# SCH_Dashboy_camera_NiMH_2023-03-14.net
KiCad netlist of a schematic drawn in EasyEDA
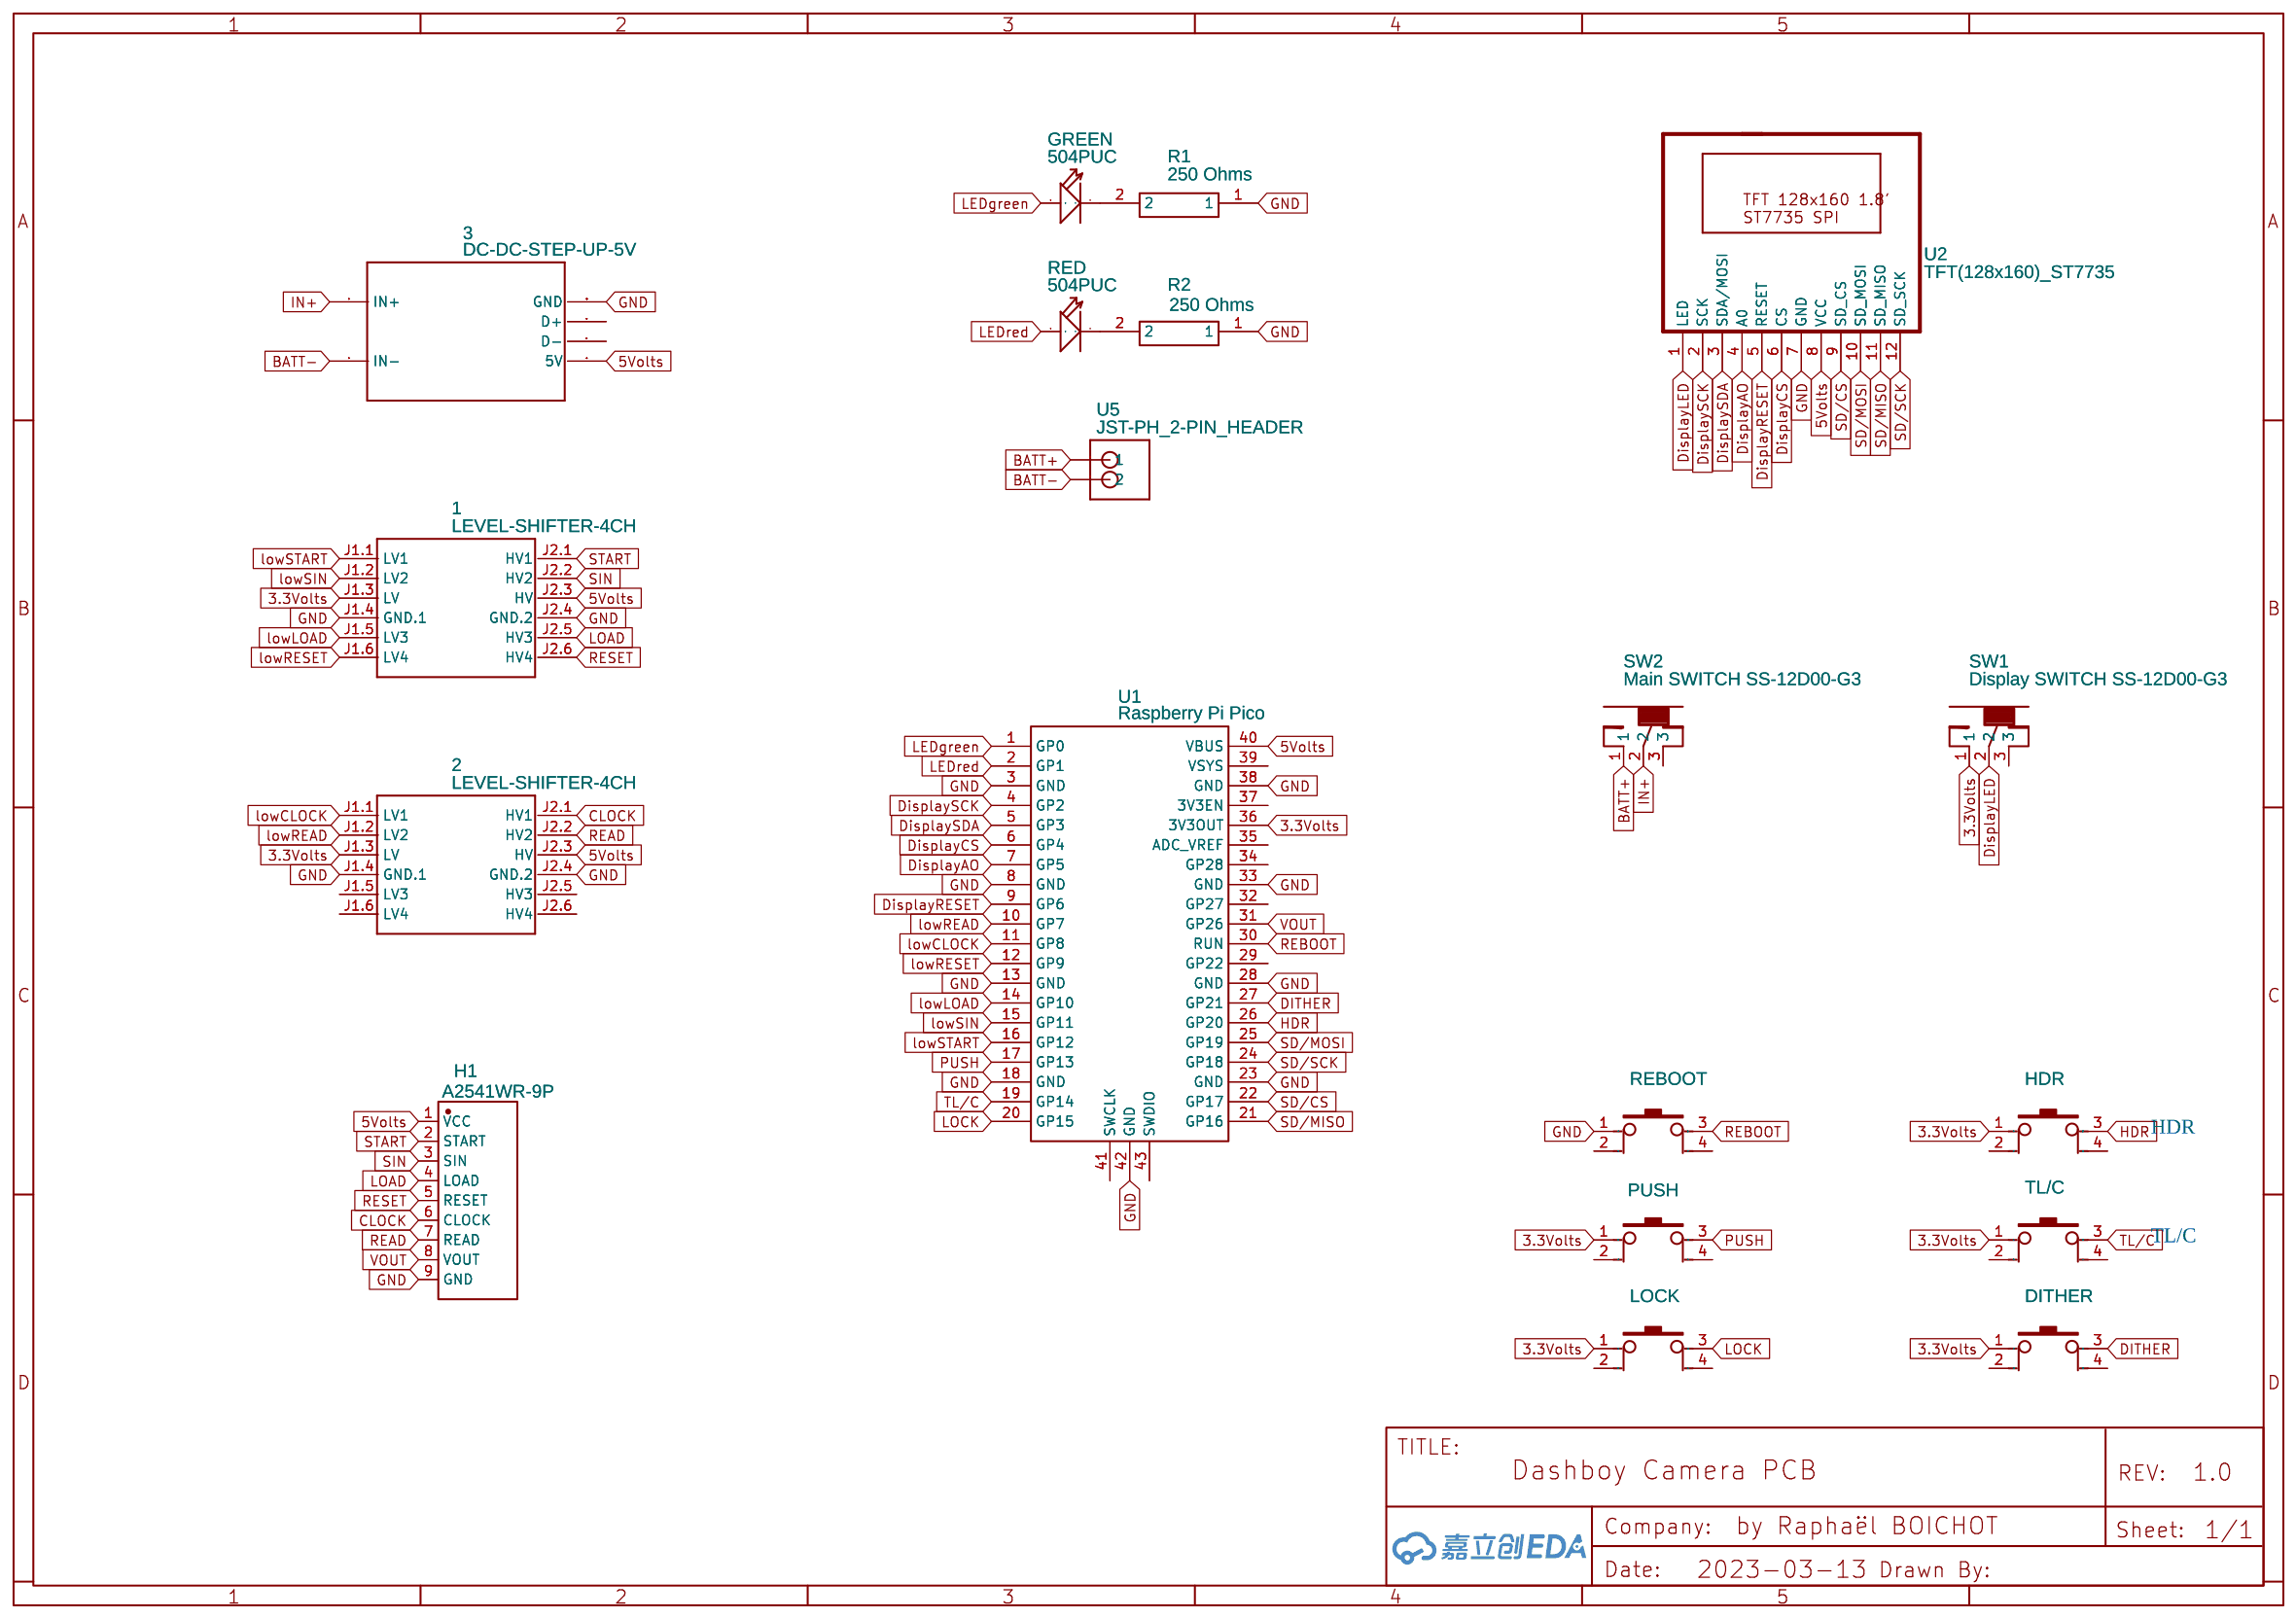
[diagram p0: schematic sheet]

(export (version "E")
  (design (tool "Eeschema 10.0.6"))
  (components
    (comp (ref "1") (value "LEVEL-SHIFTER-4CH") (libsource (lib "") (part "LEVEL-SHIFTER-4CH")))
    (comp (ref "2") (value "LEVEL-SHIFTER-4CH") (libsource (lib "") (part "LEVEL-SHIFTER-4CH")))
    (comp (ref "3") (value "DC-DC-STEP-UP-5V") (libsource (lib "") (part "DC-DC-STEP-UP-5V")))
    (comp (ref "DITHER")
      (value "BoutonPoussoir")
      (fields
        (field (name "BOM_Manufacturer Part") "button6*6*8")
        (field (name "BOM_Supplier Part") "C59982")
      )
      (libsource (lib "") (part "BoutonPoussoir_3"))
    )
    (comp (ref "GREEN") (value "504PUC") (libsource (lib "") (part "504PUC_1")))
    (comp (ref "H1")
      (value "A2541WR-9P")
      (fields (field (name "BOM_Supplier Part") "C225495"))
      (libsource (lib "") (part "A2541WR-9P"))
    )
    (comp (ref "HDR")
      (value "BoutonPoussoir")
      (fields
        (field (name "BOM_Manufacturer Part") "button6*6*8")
        (field (name "BOM_Supplier Part") "C59982")
      )
      (libsource (lib "") (part "BoutonPoussoir"))
    )
    (comp (ref "LOCK")
      (value "BoutonPoussoir")
      (fields
        (field (name "BOM_Manufacturer Part") "button6*6*8")
        (field (name "BOM_Supplier Part") "C59982")
      )
      (libsource (lib "") (part "BoutonPoussoir_5"))
    )
    (comp (ref "PUSH")
      (value "BoutonPoussoir")
      (fields
        (field (name "BOM_Manufacturer Part") "button6*6*8")
        (field (name "BOM_Supplier Part") "C59982")
      )
      (libsource (lib "") (part "BoutonPoussoir_4"))
    )
    (comp (ref "R1") (value "250 Ohms") (libsource (lib "") (part "RESITOR")))
    (comp (ref "R2") (value "250 Ohms") (libsource (lib "") (part "RESITOR")))
    (comp (ref "REBOOT")
      (value "BoutonPoussoir")
      (fields
        (field (name "BOM_Manufacturer Part") "button6*6*8")
        (field (name "BOM_Supplier Part") "C59982")
      )
      (libsource (lib "") (part "BoutonPoussoir_1"))
    )
    (comp (ref "RED") (value "504PUC") (libsource (lib "") (part "504PUC")))
    (comp (ref "SW1")
      (value "Display SWITCH SS-12D00-G3")
      (fields (field (name "BOM_Manufacturer Part") "TOGGLE SWITCH SS-12D00-G3"))
      (libsource (lib "") (part "TOGGLE SWITCH SS-12D00-G3"))
    )
    (comp (ref "SW2")
      (value "Main SWITCH SS-12D00-G3")
      (fields (field (name "BOM_Manufacturer Part") "TOGGLE SWITCH SS-12D00-G3"))
      (libsource (lib "") (part "TOGGLE SWITCH SS-12D00-G3"))
    )
    (comp (ref "TL/C")
      (value "BoutonPoussoir")
      (fields
        (field (name "BOM_Manufacturer Part") "button6*6*8")
        (field (name "BOM_Supplier Part") "C59982")
      )
      (libsource (lib "") (part "BoutonPoussoir_2"))
    )
    (comp (ref "U1") (value "Raspberry Pi Pico") (libsource (lib "") (part "Raspberry Pi Pico")))
    (comp (ref "U2") (value "TFT(128x160)_ST7735") (libsource (lib "") (part "TFT(128x160)_ST7735")))
    (comp (ref "U5") (value "JST-PH_2-PIN_HEADER") (libsource (lib "") (part "JST-PH_2-PIN_HEADER")))
  )
  (nets
    (net (code "1") (name "3.3Volts") (class "Default")
      (node (ref "1") (pin "J1.3") (pinfunction "LV_J1.3") (pintype "bidirectional"))
      (node (ref "2") (pin "J1.3") (pinfunction "LV_J1.3") (pintype "bidirectional"))
      (node (ref "DITHER") (pin "1") (pinfunction "1_1") (pintype "input"))
      (node (ref "HDR") (pin "1") (pinfunction "1_1") (pintype "input"))
      (node (ref "LOCK") (pin "1") (pinfunction "1_1") (pintype "input"))
      (node (ref "PUSH") (pin "1") (pinfunction "1_1") (pintype "input"))
      (node (ref "SW1") (pin "1") (pinfunction "1_1") (pintype "bidirectional"))
      (node (ref "TL/C") (pin "1") (pinfunction "1_1") (pintype "input"))
      (node (ref "U1") (pin "36") (pinfunction "3V3OUT_36") (pintype "unspecified"))
    )
    (net (code "2") (name "5Volts") (class "Default")
      (node (ref "1") (pin "J2.3") (pinfunction "HV_J2.3") (pintype "bidirectional"))
      (node (ref "2") (pin "J2.3") (pinfunction "HV_J2.3") (pintype "bidirectional"))
      (node (ref "3") (pin "5V") (pinfunction "5V_5V") (pintype "bidirectional"))
      (node (ref "H1") (pin "1") (pinfunction "VCC_1") (pintype "unspecified"))
      (node (ref "U1") (pin "40") (pinfunction "VBUS_40") (pintype "unspecified"))
      (node (ref "U2") (pin "8") (pinfunction "VCC_8") (pintype "input"))
    )
    (net (code "3") (name "BATT+") (class "Default")
      (node (ref "SW2") (pin "1") (pinfunction "1_1") (pintype "bidirectional"))
      (node (ref "U5") (pin "P1") (pinfunction "1_P1") (pintype "unspecified"))
    )
    (net (code "4") (name "BATT-") (class "Default")
      (node (ref "3") (pin "IN-") (pinfunction "IN-_IN-") (pintype "bidirectional"))
      (node (ref "U5") (pin "P2") (pinfunction "2_P2") (pintype "unspecified"))
    )
    (net (code "5") (name "CLOCK") (class "Default")
      (node (ref "2") (pin "J2.1") (pinfunction "HV1_J2.1") (pintype "bidirectional"))
      (node (ref "H1") (pin "6") (pinfunction "CLOCK_6") (pintype "unspecified"))
    )
    (net (code "6") (name "DITHER") (class "Default")
      (node (ref "DITHER") (pin "3") (pinfunction "3_3") (pintype "input"))
      (node (ref "U1") (pin "27") (pinfunction "GP21_27") (pintype "unspecified"))
    )
    (net (code "7") (name "DisplayAO") (class "Default")
      (node (ref "U1") (pin "7") (pinfunction "GP5_7") (pintype "unspecified"))
      (node (ref "U2") (pin "4") (pinfunction "A0_4") (pintype "input"))
    )
    (net (code "8") (name "DisplayCS") (class "Default")
      (node (ref "U1") (pin "6") (pinfunction "GP4_6") (pintype "unspecified"))
      (node (ref "U2") (pin "6") (pinfunction "CS_6") (pintype "input"))
    )
    (net (code "9") (name "DisplayLED") (class "Default")
      (node (ref "SW1") (pin "2") (pinfunction "2_2") (pintype "bidirectional"))
      (node (ref "U2") (pin "1") (pinfunction "LED_1") (pintype "passive"))
    )
    (net (code "10") (name "DisplayRESET") (class "Default")
      (node (ref "U1") (pin "9") (pinfunction "GP6_9") (pintype "unspecified"))
      (node (ref "U2") (pin "5") (pinfunction "RESET_5") (pintype "input"))
    )
    (net (code "11") (name "DisplaySCK") (class "Default")
      (node (ref "U1") (pin "4") (pinfunction "GP2_4") (pintype "unspecified"))
      (node (ref "U2") (pin "2") (pinfunction "SCK_2") (pintype "output"))
    )
    (net (code "12") (name "DisplaySDA") (class "Default")
      (node (ref "U1") (pin "5") (pinfunction "GP3_5") (pintype "unspecified"))
      (node (ref "U2") (pin "3") (pinfunction "SDA/MOSI_3") (pintype "input"))
    )
    (net (code "13") (name "GND") (class "Default")
      (node (ref "1") (pin "J1.4") (pinfunction "GND.1_J1.4") (pintype "bidirectional"))
      (node (ref "1") (pin "J2.4") (pinfunction "GND.2_J2.4") (pintype "bidirectional"))
      (node (ref "2") (pin "J1.4") (pinfunction "GND.1_J1.4") (pintype "bidirectional"))
      (node (ref "2") (pin "J2.4") (pinfunction "GND.2_J2.4") (pintype "bidirectional"))
      (node (ref "3") (pin "GND") (pinfunction "GND_GND") (pintype "bidirectional"))
      (node (ref "H1") (pin "9") (pinfunction "GND_9") (pintype "unspecified"))
      (node (ref "R1") (pin "1") (pinfunction "1_1") (pintype "unspecified"))
      (node (ref "R2") (pin "1") (pinfunction "1_1") (pintype "unspecified"))
      (node (ref "REBOOT") (pin "1") (pinfunction "1_1") (pintype "input"))
      (node (ref "U1") (pin "13") (pinfunction "GND_13") (pintype "unspecified"))
      (node (ref "U1") (pin "18") (pinfunction "GND_18") (pintype "unspecified"))
      (node (ref "U1") (pin "23") (pinfunction "GND_23") (pintype "unspecified"))
      (node (ref "U1") (pin "28") (pinfunction "GND_28") (pintype "unspecified"))
      (node (ref "U1") (pin "3") (pinfunction "GND_3") (pintype "unspecified"))
      (node (ref "U1") (pin "33") (pinfunction "GND_33") (pintype "unspecified"))
      (node (ref "U1") (pin "38") (pinfunction "GND_38") (pintype "unspecified"))
      (node (ref "U1") (pin "42") (pinfunction "GND_42") (pintype "unspecified"))
      (node (ref "U1") (pin "8") (pinfunction "GND_8") (pintype "unspecified"))
      (node (ref "U2") (pin "7") (pinfunction "GND_7") (pintype "unspecified"))
    )
    (net (code "14") (name "HDR") (class "Default")
      (node (ref "HDR") (pin "3") (pinfunction "3_3") (pintype "input"))
      (node (ref "U1") (pin "26") (pinfunction "GP20_26") (pintype "unspecified"))
    )
    (net (code "15") (name "IN+") (class "Default")
      (node (ref "3") (pin "IN+") (pinfunction "IN+_IN+") (pintype "bidirectional"))
      (node (ref "SW2") (pin "2") (pinfunction "2_2") (pintype "bidirectional"))
    )
    (net (code "16") (name "LEDgreen") (class "Default")
      (node (ref "GREEN") (pin "+") (pinfunction "+_+") (pintype "unspecified"))
      (node (ref "U1") (pin "1") (pinfunction "GP0_1") (pintype "unspecified"))
    )
    (net (code "17") (name "LEDred") (class "Default")
      (node (ref "RED") (pin "+") (pinfunction "+_+") (pintype "unspecified"))
      (node (ref "U1") (pin "2") (pinfunction "GP1_2") (pintype "unspecified"))
    )
    (net (code "18") (name "LOAD") (class "Default")
      (node (ref "1") (pin "J2.5") (pinfunction "HV3_J2.5") (pintype "bidirectional"))
      (node (ref "H1") (pin "4") (pinfunction "LOAD_4") (pintype "unspecified"))
    )
    (net (code "19") (name "LOCK") (class "Default")
      (node (ref "LOCK") (pin "3") (pinfunction "3_3") (pintype "input"))
      (node (ref "U1") (pin "20") (pinfunction "GP15_20") (pintype "unspecified"))
    )
    (net (code "20") (name "Net-(GREEN-Pad-)") (class "Default")
      (node (ref "GREEN") (pin "-") (pinfunction "-_-") (pintype "unspecified"))
      (node (ref "R1") (pin "2") (pinfunction "2_2") (pintype "unspecified"))
    )
    (net (code "21") (name "Net-(R2-Pad2)") (class "Default")
      (node (ref "R2") (pin "2") (pinfunction "2_2") (pintype "unspecified"))
      (node (ref "RED") (pin "-") (pinfunction "-_-") (pintype "unspecified"))
    )
    (net (code "22") (name "PUSH") (class "Default")
      (node (ref "PUSH") (pin "3") (pinfunction "3_3") (pintype "input"))
      (node (ref "U1") (pin "17") (pinfunction "GP13_17") (pintype "unspecified"))
    )
    (net (code "23") (name "READ") (class "Default")
      (node (ref "2") (pin "J2.2") (pinfunction "HV2_J2.2") (pintype "bidirectional"))
      (node (ref "H1") (pin "7") (pinfunction "READ_7") (pintype "unspecified"))
    )
    (net (code "24") (name "REBOOT") (class "Default")
      (node (ref "REBOOT") (pin "3") (pinfunction "3_3") (pintype "input"))
      (node (ref "U1") (pin "30") (pinfunction "RUN_30") (pintype "unspecified"))
    )
    (net (code "25") (name "RESET") (class "Default")
      (node (ref "1") (pin "J2.6") (pinfunction "HV4_J2.6") (pintype "bidirectional"))
      (node (ref "H1") (pin "5") (pinfunction "RESET_5") (pintype "unspecified"))
    )
    (net (code "26") (name "SD{slash}CS") (class "Default")
      (node (ref "U1") (pin "22") (pinfunction "GP17_22") (pintype "unspecified"))
      (node (ref "U2") (pin "9") (pinfunction "SD_CS_9") (pintype "input"))
    )
    (net (code "27") (name "SD{slash}MISO") (class "Default")
      (node (ref "U1") (pin "21") (pinfunction "GP16_21") (pintype "unspecified"))
      (node (ref "U2") (pin "11") (pinfunction "SD_MISO_11") (pintype "input"))
    )
    (net (code "28") (name "SD{slash}MOSI") (class "Default")
      (node (ref "U1") (pin "25") (pinfunction "GP19_25") (pintype "unspecified"))
      (node (ref "U2") (pin "10") (pinfunction "SD_MOSI_10") (pintype "input"))
    )
    (net (code "29") (name "SD{slash}SCK") (class "Default")
      (node (ref "U1") (pin "24") (pinfunction "GP18_24") (pintype "unspecified"))
      (node (ref "U2") (pin "12") (pinfunction "SD_SCK_12") (pintype "input"))
    )
    (net (code "30") (name "SIN") (class "Default")
      (node (ref "1") (pin "J2.2") (pinfunction "HV2_J2.2") (pintype "bidirectional"))
      (node (ref "H1") (pin "3") (pinfunction "SIN_3") (pintype "unspecified"))
    )
    (net (code "31") (name "START") (class "Default")
      (node (ref "1") (pin "J2.1") (pinfunction "HV1_J2.1") (pintype "bidirectional"))
      (node (ref "H1") (pin "2") (pinfunction "START_2") (pintype "unspecified"))
    )
    (net (code "32") (name "TL{slash}C") (class "Default")
      (node (ref "TL/C") (pin "3") (pinfunction "3_3") (pintype "input"))
      (node (ref "U1") (pin "19") (pinfunction "GP14_19") (pintype "unspecified"))
    )
    (net (code "33") (name "VOUT") (class "Default")
      (node (ref "H1") (pin "8") (pinfunction "VOUT_8") (pintype "unspecified"))
      (node (ref "U1") (pin "31") (pinfunction "GP26_31") (pintype "unspecified"))
    )
    (net (code "34") (name "lowCLOCK") (class "Default")
      (node (ref "2") (pin "J1.1") (pinfunction "LV1_J1.1") (pintype "bidirectional"))
      (node (ref "U1") (pin "11") (pinfunction "GP8_11") (pintype "unspecified"))
    )
    (net (code "35") (name "lowLOAD") (class "Default")
      (node (ref "1") (pin "J1.5") (pinfunction "LV3_J1.5") (pintype "bidirectional"))
      (node (ref "U1") (pin "14") (pinfunction "GP10_14") (pintype "unspecified"))
    )
    (net (code "36") (name "lowREAD") (class "Default")
      (node (ref "2") (pin "J1.2") (pinfunction "LV2_J1.2") (pintype "bidirectional"))
      (node (ref "U1") (pin "10") (pinfunction "GP7_10") (pintype "unspecified"))
    )
    (net (code "37") (name "lowRESET") (class "Default")
      (node (ref "1") (pin "J1.6") (pinfunction "LV4_J1.6") (pintype "bidirectional"))
      (node (ref "U1") (pin "12") (pinfunction "GP9_12") (pintype "unspecified"))
    )
    (net (code "38") (name "lowSIN") (class "Default")
      (node (ref "1") (pin "J1.2") (pinfunction "LV2_J1.2") (pintype "bidirectional"))
      (node (ref "U1") (pin "15") (pinfunction "GP11_15") (pintype "unspecified"))
    )
    (net (code "39") (name "lowSTART") (class "Default")
      (node (ref "1") (pin "J1.1") (pinfunction "LV1_J1.1") (pintype "bidirectional"))
      (node (ref "U1") (pin "16") (pinfunction "GP12_16") (pintype "unspecified"))
    )
    (net (code "40") (name "unconnected-(2-HV3-PadJ2.5)") (class "Default")
      (node (ref "2") (pin "J2.5") (pinfunction "HV3_J2.5") (pintype "bidirectional"))
    )
    (net (code "41") (name "unconnected-(2-HV4-PadJ2.6)") (class "Default")
      (node (ref "2") (pin "J2.6") (pinfunction "HV4_J2.6") (pintype "bidirectional"))
    )
    (net (code "42") (name "unconnected-(2-LV3-PadJ1.5)") (class "Default")
      (node (ref "2") (pin "J1.5") (pinfunction "LV3_J1.5") (pintype "bidirectional"))
    )
    (net (code "43") (name "unconnected-(2-LV4-PadJ1.6)") (class "Default")
      (node (ref "2") (pin "J1.6") (pinfunction "LV4_J1.6") (pintype "bidirectional"))
    )
    (net (code "44") (name "unconnected-(3-PadD+)") (class "Default")
      (node (ref "3") (pin "D+") (pinfunction "D+_D+") (pintype "bidirectional"))
    )
    (net (code "45") (name "unconnected-(3-PadD-)") (class "Default")
      (node (ref "3") (pin "D-") (pinfunction "D-_D-") (pintype "bidirectional"))
    )
    (net (code "46") (name "unconnected-(DITHER-Pad2)") (class "Default")
      (node (ref "DITHER") (pin "2") (pinfunction "2_2") (pintype "input"))
    )
    (net (code "47") (name "unconnected-(DITHER-Pad4)") (class "Default")
      (node (ref "DITHER") (pin "4") (pinfunction "4_4") (pintype "input"))
    )
    (net (code "48") (name "unconnected-(HDR-Pad2)") (class "Default")
      (node (ref "HDR") (pin "2") (pinfunction "2_2") (pintype "input"))
    )
    (net (code "49") (name "unconnected-(HDR-Pad4)") (class "Default")
      (node (ref "HDR") (pin "4") (pinfunction "4_4") (pintype "input"))
    )
    (net (code "50") (name "unconnected-(LOCK-Pad2)") (class "Default")
      (node (ref "LOCK") (pin "2") (pinfunction "2_2") (pintype "input"))
    )
    (net (code "51") (name "unconnected-(LOCK-Pad4)") (class "Default")
      (node (ref "LOCK") (pin "4") (pinfunction "4_4") (pintype "input"))
    )
    (net (code "52") (name "unconnected-(PUSH-Pad2)") (class "Default")
      (node (ref "PUSH") (pin "2") (pinfunction "2_2") (pintype "input"))
    )
    (net (code "53") (name "unconnected-(PUSH-Pad4)") (class "Default")
      (node (ref "PUSH") (pin "4") (pinfunction "4_4") (pintype "input"))
    )
    (net (code "54") (name "unconnected-(REBOOT-Pad2)") (class "Default")
      (node (ref "REBOOT") (pin "2") (pinfunction "2_2") (pintype "input"))
    )
    (net (code "55") (name "unconnected-(REBOOT-Pad4)") (class "Default")
      (node (ref "REBOOT") (pin "4") (pinfunction "4_4") (pintype "input"))
    )
    (net (code "56") (name "unconnected-(SW1-Pad3)") (class "Default")
      (node (ref "SW1") (pin "3") (pinfunction "3_3") (pintype "unspecified"))
    )
    (net (code "57") (name "unconnected-(SW2-Pad3)") (class "Default")
      (node (ref "SW2") (pin "3") (pinfunction "3_3") (pintype "unspecified"))
    )
    (net (code "58") (name "unconnected-(TL/C-Pad2)") (class "Default")
      (node (ref "TL/C") (pin "2") (pinfunction "2_2") (pintype "input"))
    )
    (net (code "59") (name "unconnected-(TL/C-Pad4)") (class "Default")
      (node (ref "TL/C") (pin "4") (pinfunction "4_4") (pintype "input"))
    )
    (net (code "60") (name "unconnected-(U1-3V3EN-Pad37)") (class "Default")
      (node (ref "U1") (pin "37") (pinfunction "3V3EN_37") (pintype "unspecified"))
    )
    (net (code "61") (name "unconnected-(U1-ADC_VREF-Pad35)") (class "Default")
      (node (ref "U1") (pin "35") (pinfunction "ADC_VREF_35") (pintype "unspecified"))
    )
    (net (code "62") (name "unconnected-(U1-GP22-Pad29)") (class "Default")
      (node (ref "U1") (pin "29") (pinfunction "GP22_29") (pintype "unspecified"))
    )
    (net (code "63") (name "unconnected-(U1-GP27-Pad32)") (class "Default")
      (node (ref "U1") (pin "32") (pinfunction "GP27_32") (pintype "unspecified"))
    )
    (net (code "64") (name "unconnected-(U1-GP28-Pad34)") (class "Default")
      (node (ref "U1") (pin "34") (pinfunction "GP28_34") (pintype "unspecified"))
    )
    (net (code "65") (name "unconnected-(U1-SWCLK-Pad41)") (class "Default")
      (node (ref "U1") (pin "41") (pinfunction "SWCLK_41") (pintype "unspecified"))
    )
    (net (code "66") (name "unconnected-(U1-SWDIO-Pad43)") (class "Default")
      (node (ref "U1") (pin "43") (pinfunction "SWDIO_43") (pintype "unspecified"))
    )
    (net (code "67") (name "unconnected-(U1-VSYS-Pad39)") (class "Default")
      (node (ref "U1") (pin "39") (pinfunction "VSYS_39") (pintype "unspecified"))
    )
  )
)
